# EMP3.net
KiCad netlist of a schematic drawn in EAGLE
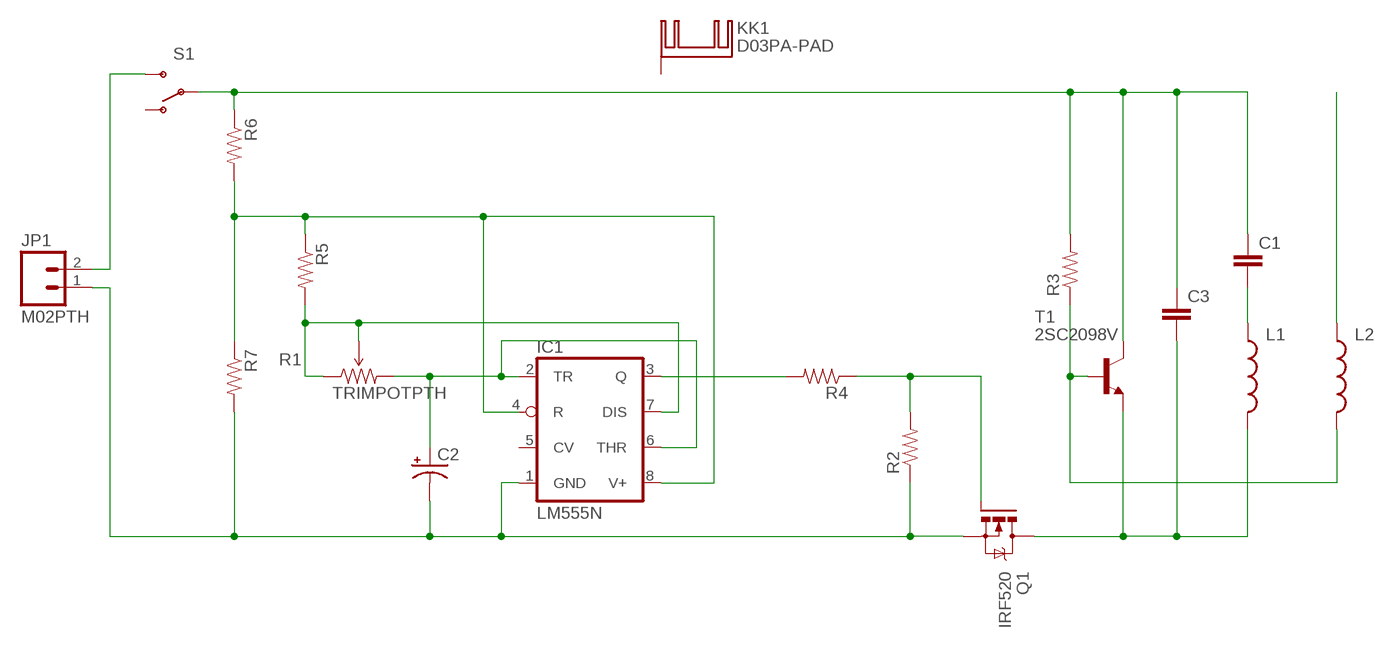
[diagram p0: schematic, sheet 1]

(export (version "E")
  (design (tool "Eeschema 10.0.6"))
  (components
    (comp (ref "C1")
      (value "CAPEZ")
      (footprint "eagle-import:CAP-PTH-SMALLEZ")
      (libsource (lib "eagle-import") (part "CAPEZ"))
    )
    (comp (ref "C2")
      (value "CAP_POLPTH2")
      (footprint "eagle-import:CPOL-RADIAL-10UF-25V")
      (libsource (lib "eagle-import") (part "CAP_POLPTH2"))
    )
    (comp (ref "C3")
      (value "CAPEZ")
      (footprint "eagle-import:CAP-PTH-SMALLEZ")
      (libsource (lib "eagle-import") (part "CAPEZ"))
    )
    (comp (ref "IC1")
      (value "LM555N")
      (footprint "eagle-import:DIL08-ROUND")
      (libsource (lib "eagle-import") (part "555NLM"))
    )
    (comp (ref "JP1")
      (value "M02PTH")
      (footprint "eagle-import:1X02")
      (libsource (lib "eagle-import") (part "M02PTH"))
    )
    (comp (ref "KK1")
      (value "D03PA-PAD")
      (footprint "eagle-import:D03PA-PAD")
      (libsource (lib "eagle-import") (part "D03PA-PAD"))
    )
    (comp (ref "L1")
      (value "INDUCTORCR54-KIT")
      (footprint "eagle-import:CR54-KIT")
      (libsource (lib "eagle-import") (part "INDUCTORCR54-KIT"))
    )
    (comp (ref "L2")
      (value "INDUCTORCR54-KIT")
      (footprint "eagle-import:CR54-KIT")
      (libsource (lib "eagle-import") (part "INDUCTORCR54-KIT"))
    )
    (comp (ref "Q1")
      (value "IRF520")
      (footprint "eagle-import:TO220BV")
      (libsource (lib "eagle-import") (part "IRF520"))
    )
    (comp (ref "R1")
      (value "TRIMPOTPTH")
      (footprint "eagle-import:TRIM_POT_PTH")
      (libsource (lib "eagle-import") (part "TRIMPOTPTH"))
    )
    (comp (ref "R2")
      (value "RESISTOREZ")
      (footprint "eagle-import:AXIAL-0.3EZ")
      (libsource (lib "eagle-import") (part "RESISTOREZ"))
    )
    (comp (ref "R3")
      (value "RESISTOREZ")
      (footprint "eagle-import:AXIAL-0.3EZ")
      (libsource (lib "eagle-import") (part "RESISTOREZ"))
    )
    (comp (ref "R4")
      (value "RESISTOREZ")
      (footprint "eagle-import:AXIAL-0.3EZ")
      (libsource (lib "eagle-import") (part "RESISTOREZ"))
    )
    (comp (ref "R5")
      (value "RESISTOREZ")
      (footprint "eagle-import:AXIAL-0.3EZ")
      (libsource (lib "eagle-import") (part "RESISTOREZ"))
    )
    (comp (ref "R6")
      (value "RESISTOREZ")
      (footprint "eagle-import:AXIAL-0.3EZ")
      (libsource (lib "eagle-import") (part "RESISTOREZ"))
    )
    (comp (ref "R7")
      (value "RESISTOREZ")
      (footprint "eagle-import:AXIAL-0.3EZ")
      (libsource (lib "eagle-import") (part "RESISTOREZ"))
    )
    (comp (ref "S1")
      (value "SWITCH-SPDTPTH")
      (footprint "eagle-import:SWITCH-SPDT")
      (libsource (lib "eagle-import") (part "SWITCH-SPDTPTH"))
    )
    (comp (ref "T1")
      (value "2SC2098V")
      (footprint "eagle-import:TO220AV")
      (libsource (lib "eagle-import") (part "2SC2098V"))
    )
  )
  (nets
    (net (code "1") (name "Net-(C2-+)") (class "Default")
      (node (ref "C2") (pin "1") (pinfunction "+_1") (pintype "passive"))
      (node (ref "IC1") (pin "2") (pinfunction "TR_2") (pintype "input"))
      (node (ref "IC1") (pin "6") (pinfunction "THR_6") (pintype "input"))
      (node (ref "R1") (pin "3") (pinfunction "CW_3") (pintype "passive"))
    )
    (net (code "2") (name "Net-(C2--)") (class "Default")
      (node (ref "C2") (pin "2") (pinfunction "-_2") (pintype "passive"))
      (node (ref "IC1") (pin "1") (pinfunction "GND_1") (pintype "power_in"))
      (node (ref "JP1") (pin "1") (pinfunction "1_1") (pintype "passive"))
      (node (ref "Q1") (pin "S") (pinfunction "S_S") (pintype "passive"))
      (node (ref "R2") (pin "P$1") (pinfunction "1_P$1") (pintype "passive"))
      (node (ref "R7") (pin "P$2") (pinfunction "2_P$2") (pintype "passive"))
    )
    (net (code "3") (name "Net-(IC1-DIS)") (class "Default")
      (node (ref "IC1") (pin "7") (pinfunction "DIS_7") (pintype "input"))
      (node (ref "R1") (pin "1") (pinfunction "CCW_1") (pintype "passive"))
      (node (ref "R1") (pin "2") (pinfunction "WIPER_2") (pintype "passive"))
      (node (ref "R5") (pin "P$2") (pinfunction "2_P$2") (pintype "passive"))
    )
    (net (code "4") (name "Net-(IC1-Q)") (class "Default")
      (node (ref "IC1") (pin "3") (pinfunction "Q_3") (pintype "output"))
      (node (ref "R4") (pin "P$2") (pinfunction "2_P$2") (pintype "passive"))
    )
    (net (code "5") (name "Net-(IC1-R)") (class "Default")
      (node (ref "IC1") (pin "4") (pinfunction "R_4") (pintype "input"))
      (node (ref "IC1") (pin "8") (pinfunction "V+_8") (pintype "power_in"))
      (node (ref "R5") (pin "P$1") (pinfunction "1_P$1") (pintype "passive"))
      (node (ref "R6") (pin "P$2") (pinfunction "2_P$2") (pintype "passive"))
      (node (ref "R7") (pin "P$1") (pinfunction "1_P$1") (pintype "passive"))
    )
    (net (code "6") (name "Net-(L1-1)") (class "Default")
      (node (ref "C1") (pin "2") (pinfunction "2_2") (pintype "passive"))
      (node (ref "L1") (pin "P$1") (pinfunction "1_P$1") (pintype "passive"))
    )
    (net (code "7") (name "Net-(L1-2)") (class "Default")
      (node (ref "C3") (pin "2") (pinfunction "2_2") (pintype "passive"))
      (node (ref "L1") (pin "P$2") (pinfunction "2_P$2") (pintype "passive"))
      (node (ref "Q1") (pin "D") (pinfunction "D_D") (pintype "passive"))
      (node (ref "T1") (pin "3") (pinfunction "E_3") (pintype "passive"))
    )
    (net (code "8") (name "Net-(L2-2)") (class "Default")
      (node (ref "L2") (pin "P$2") (pinfunction "2_P$2") (pintype "passive"))
      (node (ref "R3") (pin "P$1") (pinfunction "1_P$1") (pintype "passive"))
      (node (ref "T1") (pin "1") (pinfunction "B_1") (pintype "passive"))
    )
    (net (code "9") (name "Net-(R2-2)") (class "Default")
      (node (ref "Q1") (pin "G") (pinfunction "G_G") (pintype "passive"))
      (node (ref "R2") (pin "P$2") (pinfunction "2_P$2") (pintype "passive"))
      (node (ref "R4") (pin "P$1") (pinfunction "1_P$1") (pintype "passive"))
    )
    (net (code "10") (name "Net-(R3-2)") (class "Default")
      (node (ref "C1") (pin "1") (pinfunction "1_1") (pintype "passive"))
      (node (ref "C3") (pin "1") (pinfunction "1_1") (pintype "passive"))
      (node (ref "R3") (pin "P$2") (pinfunction "2_P$2") (pintype "passive"))
      (node (ref "R6") (pin "P$1") (pinfunction "1_P$1") (pintype "passive"))
      (node (ref "S1") (pin "2") (pinfunction "P_2") (pintype "passive"))
      (node (ref "T1") (pin "2") (pinfunction "C_2") (pintype "passive"))
    )
    (net (code "11") (name "Net-(S1-S)") (class "Default")
      (node (ref "JP1") (pin "2") (pinfunction "2_2") (pintype "passive"))
      (node (ref "S1") (pin "3") (pinfunction "S_3") (pintype "passive"))
    )
    (net (code "12") (name "unconnected-(IC1-CV-Pad5)") (class "Default")
      (node (ref "IC1") (pin "5") (pinfunction "CV_5") (pintype "input"))
    )
    (net (code "13") (name "unconnected-(KK1-K-PadB)") (class "Default")
      (node (ref "KK1") (pin "B") (pinfunction "K_B") (pintype "passive"))
    )
    (net (code "14") (name "unconnected-(L2-1-PadP$1)") (class "Default")
      (node (ref "L2") (pin "P$1") (pinfunction "1_P$1") (pintype "passive"))
    )
    (net (code "15") (name "unconnected-(S1-O-Pad1)") (class "Default")
      (node (ref "S1") (pin "1") (pinfunction "O_1") (pintype "passive"))
    )
  )
)
